# receiver_v2.net
KiCad netlist of a schematic drawn in EAGLE
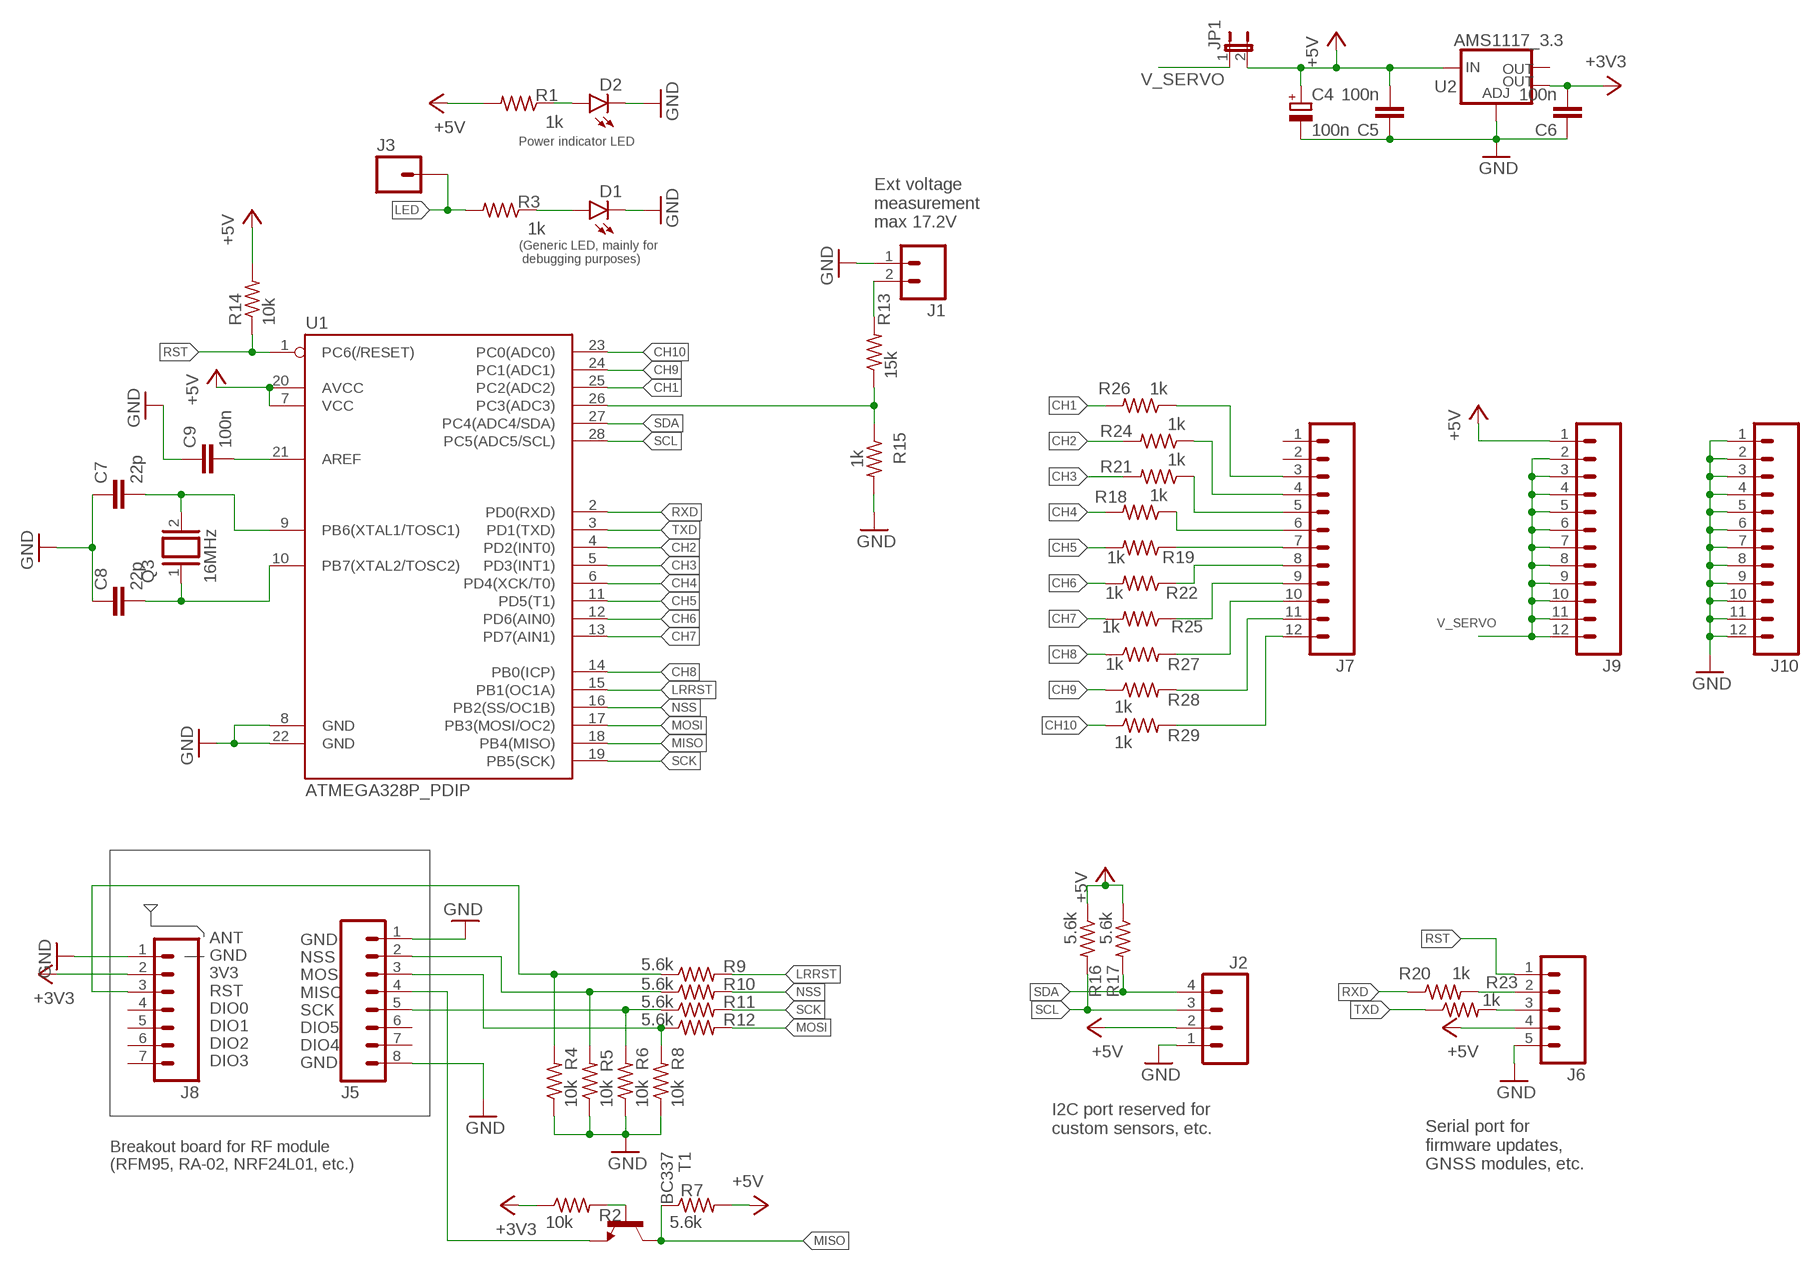
[diagram p0: schematic, sheet 1]

(export (version "E")
  (design (tool "Eeschema 10.0.6"))
  (components
    (comp (ref "C4")
      (value "100n")
      (footprint "eagle-import:E2,5-6E")
      (libsource (lib "eagle-import") (part "CPOL-EUE2,5-6E"))
    )
    (comp (ref "C5")
      (value "100n")
      (footprint "eagle-import:C050-024X044")
      (libsource (lib "eagle-import") (part "C-EU050-024X044"))
    )
    (comp (ref "C6")
      (value "100n")
      (footprint "eagle-import:C050-024X044")
      (libsource (lib "eagle-import") (part "C-EU050-024X044"))
    )
    (comp (ref "C7")
      (value "22p")
      (footprint "eagle-import:C050-024X044")
      (libsource (lib "eagle-import") (part "C-EU050-024X044"))
    )
    (comp (ref "C8")
      (value "22p")
      (footprint "eagle-import:C050-024X044")
      (libsource (lib "eagle-import") (part "C-EU050-024X044"))
    )
    (comp (ref "C9")
      (value "100n")
      (footprint "eagle-import:C050-024X044")
      (libsource (lib "eagle-import") (part "C-EU050-024X044"))
    )
    (comp (ref "D1")
      (value "LED3MM")
      (footprint "eagle-import:LED3MM")
      (libsource (lib "eagle-import") (part "LED3MM"))
    )
    (comp (ref "D2")
      (value "LED3MM")
      (footprint "eagle-import:LED3MM")
      (libsource (lib "eagle-import") (part "LED3MM"))
    )
    (comp (ref "J1")
      (value "M02PTH")
      (footprint "eagle-import:1X02")
      (libsource (lib "eagle-import") (part "M02PTH"))
    )
    (comp (ref "J2")
      (value "M04PTH")
      (footprint "eagle-import:1X04")
      (libsource (lib "eagle-import") (part "M04PTH"))
    )
    (comp (ref "J3")
      (value "M01PTH")
      (footprint "eagle-import:1X01")
      (libsource (lib "eagle-import") (part "M01PTH"))
    )
    (comp (ref "J5")
      (value "M08")
      (footprint "eagle-import:1X08_ROUND")
      (libsource (lib "eagle-import") (part "M08"))
    )
    (comp (ref "J6")
      (value "M05PTH")
      (footprint "eagle-import:1X05")
      (libsource (lib "eagle-import") (part "M05PTH"))
    )
    (comp (ref "J7")
      (value "M12PTH")
      (footprint "eagle-import:1X12")
      (libsource (lib "eagle-import") (part "M12PTH"))
    )
    (comp (ref "J8")
      (value "M07")
      (footprint "eagle-import:1X07")
      (libsource (lib "eagle-import") (part "M07"))
    )
    (comp (ref "J9")
      (value "M12PTH")
      (footprint "eagle-import:1X12")
      (libsource (lib "eagle-import") (part "M12PTH"))
    )
    (comp (ref "J10")
      (value "M12PTH")
      (footprint "eagle-import:1X12")
      (libsource (lib "eagle-import") (part "M12PTH"))
    )
    (comp (ref "JP1")
      (value "JP1E")
      (footprint "eagle-import:JP1")
      (libsource (lib "eagle-import") (part "JP1E"))
    )
    (comp (ref "Q3")
      (value "16MHz")
      (footprint "eagle-import:QS")
      (libsource (lib "eagle-import") (part "XTAL/S"))
    )
    (comp (ref "R1")
      (value "1k")
      (footprint "eagle-import:0204V")
      (libsource (lib "eagle-import") (part "R-US_0204/2V"))
    )
    (comp (ref "R2")
      (value "10k")
      (footprint "eagle-import:0207_15")
      (libsource (lib "eagle-import") (part "R-US_0207/15"))
    )
    (comp (ref "R3")
      (value "1k")
      (footprint "eagle-import:0204V")
      (libsource (lib "eagle-import") (part "R-US_0204/2V"))
    )
    (comp (ref "R4")
      (value "10k")
      (footprint "eagle-import:0204V")
      (libsource (lib "eagle-import") (part "R-US_0204/2V"))
    )
    (comp (ref "R5")
      (value "10k")
      (footprint "eagle-import:0204V")
      (libsource (lib "eagle-import") (part "R-US_0204/2V"))
    )
    (comp (ref "R6")
      (value "10k")
      (footprint "eagle-import:0204V")
      (libsource (lib "eagle-import") (part "R-US_0204/2V"))
    )
    (comp (ref "R7")
      (value "5.6k")
      (footprint "eagle-import:0204V")
      (libsource (lib "eagle-import") (part "R-US_0204/2V"))
    )
    (comp (ref "R8")
      (value "10k")
      (footprint "eagle-import:0204V")
      (libsource (lib "eagle-import") (part "R-US_0204/2V"))
    )
    (comp (ref "R9")
      (value "5.6k")
      (footprint "eagle-import:0204V")
      (libsource (lib "eagle-import") (part "R-US_0204/2V"))
    )
    (comp (ref "R10")
      (value "5.6k")
      (footprint "eagle-import:0204V")
      (libsource (lib "eagle-import") (part "R-US_0204/2V"))
    )
    (comp (ref "R11")
      (value "5.6k")
      (footprint "eagle-import:0204V")
      (libsource (lib "eagle-import") (part "R-US_0204/2V"))
    )
    (comp (ref "R12")
      (value "5.6k")
      (footprint "eagle-import:0204V")
      (libsource (lib "eagle-import") (part "R-US_0204/2V"))
    )
    (comp (ref "R13")
      (value "15k")
      (footprint "eagle-import:0204V")
      (libsource (lib "eagle-import") (part "R-US_0204/2V"))
    )
    (comp (ref "R14")
      (value "10k")
      (footprint "eagle-import:0204_7")
      (libsource (lib "eagle-import") (part "R-US_0204/7"))
    )
    (comp (ref "R15")
      (value "1k")
      (footprint "eagle-import:0204V")
      (libsource (lib "eagle-import") (part "R-US_0204/2V"))
    )
    (comp (ref "R16")
      (value "5.6k")
      (footprint "eagle-import:0204V")
      (libsource (lib "eagle-import") (part "R-US_0204/2V"))
    )
    (comp (ref "R17")
      (value "5.6k")
      (footprint "eagle-import:0204V")
      (libsource (lib "eagle-import") (part "R-US_0204/2V"))
    )
    (comp (ref "R18")
      (value "1k")
      (footprint "eagle-import:0204V")
      (libsource (lib "eagle-import") (part "R-US_0204/2V"))
    )
    (comp (ref "R19")
      (value "1k")
      (footprint "eagle-import:0204V")
      (libsource (lib "eagle-import") (part "R-US_0204/2V"))
    )
    (comp (ref "R20")
      (value "1k")
      (footprint "eagle-import:0204_7")
      (libsource (lib "eagle-import") (part "R-US_0204/7"))
    )
    (comp (ref "R21")
      (value "1k")
      (footprint "eagle-import:0204V")
      (libsource (lib "eagle-import") (part "R-US_0204/2V"))
    )
    (comp (ref "R22")
      (value "1k")
      (footprint "eagle-import:0204V")
      (libsource (lib "eagle-import") (part "R-US_0204/2V"))
    )
    (comp (ref "R23")
      (value "1k")
      (footprint "eagle-import:0204_7")
      (libsource (lib "eagle-import") (part "R-US_0204/7"))
    )
    (comp (ref "R24")
      (value "1k")
      (footprint "eagle-import:0204V")
      (libsource (lib "eagle-import") (part "R-US_0204/2V"))
    )
    (comp (ref "R25")
      (value "1k")
      (footprint "eagle-import:0204V")
      (libsource (lib "eagle-import") (part "R-US_0204/2V"))
    )
    (comp (ref "R26")
      (value "1k")
      (footprint "eagle-import:0204V")
      (libsource (lib "eagle-import") (part "R-US_0204/2V"))
    )
    (comp (ref "R27")
      (value "1k")
      (footprint "eagle-import:0204V")
      (libsource (lib "eagle-import") (part "R-US_0204/2V"))
    )
    (comp (ref "R28")
      (value "1k")
      (footprint "eagle-import:0204V")
      (libsource (lib "eagle-import") (part "R-US_0204/2V"))
    )
    (comp (ref "R29")
      (value "1k")
      (footprint "eagle-import:0204V")
      (libsource (lib "eagle-import") (part "R-US_0204/2V"))
    )
    (comp (ref "T1")
      (value "BC337")
      (footprint "eagle-import:TO92")
      (libsource (lib "eagle-import") (part "BC337"))
    )
    (comp (ref "U1")
      (value "ATMEGA328P_PDIP")
      (footprint "eagle-import:DIL28-3")
      (libsource (lib "eagle-import") (part "ATMEGA328P_PDIP"))
    )
    (comp (ref "U2")
      (value "AMS1117_3.3")
      (footprint "eagle-import:SOT223")
      (libsource (lib "eagle-import") (part "V_REG_LM1117SOT223"))
    )
  )
  (nets
    (net (code "1") (name "+3V3") (class "Default")
      (node (ref "C6") (pin "2") (pinfunction "2_2") (pintype "passive"))
      (node (ref "J8") (pin "2") (pinfunction "2_2") (pintype "passive"))
      (node (ref "R2") (pin "1") (pinfunction "1_1") (pintype "passive"))
      (node (ref "U2") (pin "4") (pinfunction "OUT_4") (pintype "output"))
    )
    (net (code "2") (name "+5V") (class "Default")
      (node (ref "C4") (pin "+") (pinfunction "+_+") (pintype "passive"))
      (node (ref "C5") (pin "2") (pinfunction "2_2") (pintype "passive"))
      (node (ref "J2") (pin "2") (pinfunction "2_2") (pintype "passive"))
      (node (ref "J6") (pin "4") (pinfunction "4_4") (pintype "passive"))
      (node (ref "J9") (pin "1") (pinfunction "1_1") (pintype "passive"))
      (node (ref "JP1") (pin "2") (pinfunction "2_2") (pintype "passive"))
      (node (ref "R1") (pin "2") (pinfunction "2_2") (pintype "passive"))
      (node (ref "R14") (pin "2") (pinfunction "2_2") (pintype "passive"))
      (node (ref "R16") (pin "1") (pinfunction "1_1") (pintype "passive"))
      (node (ref "R17") (pin "1") (pinfunction "1_1") (pintype "passive"))
      (node (ref "R7") (pin "2") (pinfunction "2_2") (pintype "passive"))
      (node (ref "U1") (pin "20") (pinfunction "AVCC_20") (pintype "bidirectional"))
      (node (ref "U1") (pin "7") (pinfunction "VCC_7") (pintype "bidirectional"))
      (node (ref "U2") (pin "3") (pinfunction "IN_3") (pintype "input"))
    )
    (net (code "3") (name "/V_SERVO") (class "Default")
      (node (ref "J9") (pin "10") (pinfunction "10_10") (pintype "passive"))
      (node (ref "J9") (pin "11") (pinfunction "11_11") (pintype "passive"))
      (node (ref "J9") (pin "12") (pinfunction "12_12") (pintype "passive"))
      (node (ref "J9") (pin "2") (pinfunction "2_2") (pintype "passive"))
      (node (ref "J9") (pin "3") (pinfunction "3_3") (pintype "passive"))
      (node (ref "J9") (pin "4") (pinfunction "4_4") (pintype "passive"))
      (node (ref "J9") (pin "5") (pinfunction "5_5") (pintype "passive"))
      (node (ref "J9") (pin "6") (pinfunction "6_6") (pintype "passive"))
      (node (ref "J9") (pin "7") (pinfunction "7_7") (pintype "passive"))
      (node (ref "J9") (pin "8") (pinfunction "8_8") (pintype "passive"))
      (node (ref "J9") (pin "9") (pinfunction "9_9") (pintype "passive"))
      (node (ref "JP1") (pin "1") (pinfunction "1_1") (pintype "passive"))
    )
    (net (code "4") (name "CH1") (class "Default")
      (node (ref "R26") (pin "2") (pinfunction "2_2") (pintype "passive"))
      (node (ref "U1") (pin "25") (pinfunction "PC2(ADC2)_25") (pintype "bidirectional"))
    )
    (net (code "5") (name "CH2") (class "Default")
      (node (ref "R24") (pin "2") (pinfunction "2_2") (pintype "passive"))
      (node (ref "U1") (pin "4") (pinfunction "PD2(INT0)_4") (pintype "bidirectional"))
    )
    (net (code "6") (name "CH3") (class "Default")
      (node (ref "R21") (pin "2") (pinfunction "2_2") (pintype "passive"))
      (node (ref "U1") (pin "5") (pinfunction "PD3(INT1)_5") (pintype "bidirectional"))
    )
    (net (code "7") (name "CH4") (class "Default")
      (node (ref "R18") (pin "2") (pinfunction "2_2") (pintype "passive"))
      (node (ref "U1") (pin "6") (pinfunction "PD4(XCK/T0)_6") (pintype "bidirectional"))
    )
    (net (code "8") (name "CH5") (class "Default")
      (node (ref "R19") (pin "2") (pinfunction "2_2") (pintype "passive"))
      (node (ref "U1") (pin "11") (pinfunction "PD5(T1)_11") (pintype "bidirectional"))
    )
    (net (code "9") (name "CH6") (class "Default")
      (node (ref "R22") (pin "2") (pinfunction "2_2") (pintype "passive"))
      (node (ref "U1") (pin "12") (pinfunction "PD6(AIN0)_12") (pintype "bidirectional"))
    )
    (net (code "10") (name "CH7") (class "Default")
      (node (ref "R25") (pin "2") (pinfunction "2_2") (pintype "passive"))
      (node (ref "U1") (pin "13") (pinfunction "PD7(AIN1)_13") (pintype "bidirectional"))
    )
    (net (code "11") (name "CH8") (class "Default")
      (node (ref "R27") (pin "1") (pinfunction "1_1") (pintype "passive"))
      (node (ref "U1") (pin "14") (pinfunction "PB0(ICP)_14") (pintype "bidirectional"))
    )
    (net (code "12") (name "CH9") (class "Default")
      (node (ref "R28") (pin "1") (pinfunction "1_1") (pintype "passive"))
      (node (ref "U1") (pin "24") (pinfunction "PC1(ADC1)_24") (pintype "bidirectional"))
    )
    (net (code "13") (name "CH10") (class "Default")
      (node (ref "R29") (pin "1") (pinfunction "1_1") (pintype "passive"))
      (node (ref "U1") (pin "23") (pinfunction "PC0(ADC0)_23") (pintype "bidirectional"))
    )
    (net (code "14") (name "GND") (class "Default")
      (node (ref "C4") (pin "-") (pinfunction "-_-") (pintype "passive"))
      (node (ref "C5") (pin "1") (pinfunction "1_1") (pintype "passive"))
      (node (ref "C6") (pin "1") (pinfunction "1_1") (pintype "passive"))
      (node (ref "C7") (pin "1") (pinfunction "1_1") (pintype "passive"))
      (node (ref "C8") (pin "1") (pinfunction "1_1") (pintype "passive"))
      (node (ref "C9") (pin "1") (pinfunction "1_1") (pintype "passive"))
      (node (ref "D1") (pin "K") (pinfunction "C_K") (pintype "passive"))
      (node (ref "D2") (pin "K") (pinfunction "C_K") (pintype "passive"))
      (node (ref "J1") (pin "1") (pinfunction "1_1") (pintype "passive"))
      (node (ref "J10") (pin "1") (pinfunction "1_1") (pintype "passive"))
      (node (ref "J10") (pin "10") (pinfunction "10_10") (pintype "passive"))
      (node (ref "J10") (pin "11") (pinfunction "11_11") (pintype "passive"))
      (node (ref "J10") (pin "12") (pinfunction "12_12") (pintype "passive"))
      (node (ref "J10") (pin "2") (pinfunction "2_2") (pintype "passive"))
      (node (ref "J10") (pin "3") (pinfunction "3_3") (pintype "passive"))
      (node (ref "J10") (pin "4") (pinfunction "4_4") (pintype "passive"))
      (node (ref "J10") (pin "5") (pinfunction "5_5") (pintype "passive"))
      (node (ref "J10") (pin "6") (pinfunction "6_6") (pintype "passive"))
      (node (ref "J10") (pin "7") (pinfunction "7_7") (pintype "passive"))
      (node (ref "J10") (pin "8") (pinfunction "8_8") (pintype "passive"))
      (node (ref "J10") (pin "9") (pinfunction "9_9") (pintype "passive"))
      (node (ref "J2") (pin "1") (pinfunction "1_1") (pintype "passive"))
      (node (ref "J5") (pin "1") (pinfunction "1_1") (pintype "passive"))
      (node (ref "J5") (pin "8") (pinfunction "8_8") (pintype "passive"))
      (node (ref "J6") (pin "5") (pinfunction "5_5") (pintype "passive"))
      (node (ref "J8") (pin "1") (pinfunction "1_1") (pintype "passive"))
      (node (ref "R15") (pin "2") (pinfunction "2_2") (pintype "passive"))
      (node (ref "R4") (pin "1") (pinfunction "1_1") (pintype "passive"))
      (node (ref "R5") (pin "1") (pinfunction "1_1") (pintype "passive"))
      (node (ref "R6") (pin "1") (pinfunction "1_1") (pintype "passive"))
      (node (ref "R8") (pin "1") (pinfunction "1_1") (pintype "passive"))
      (node (ref "U1") (pin "22") (pinfunction "GND_22") (pintype "bidirectional"))
      (node (ref "U1") (pin "8") (pinfunction "GND_8") (pintype "bidirectional"))
      (node (ref "U2") (pin "1") (pinfunction "ADJ_1") (pintype "input"))
    )
    (net (code "15") (name "LED") (class "Default")
      (node (ref "J3") (pin "1") (pinfunction "1_1") (pintype "passive"))
      (node (ref "R3") (pin "2") (pinfunction "2_2") (pintype "passive"))
    )
    (net (code "16") (name "LRRST") (class "Default")
      (node (ref "R9") (pin "2") (pinfunction "2_2") (pintype "passive"))
      (node (ref "U1") (pin "15") (pinfunction "PB1(OC1A)_15") (pintype "bidirectional"))
    )
    (net (code "17") (name "MISO") (class "Default")
      (node (ref "R7") (pin "1") (pinfunction "1_1") (pintype "passive"))
      (node (ref "T1") (pin "3") (pinfunction "C_3") (pintype "passive"))
      (node (ref "U1") (pin "18") (pinfunction "PB4(MISO)_18") (pintype "bidirectional"))
    )
    (net (code "18") (name "MOSI") (class "Default")
      (node (ref "R12") (pin "2") (pinfunction "2_2") (pintype "passive"))
      (node (ref "U1") (pin "17") (pinfunction "PB3(MOSI/OC2)_17") (pintype "bidirectional"))
    )
    (net (code "19") (name "NSS") (class "Default")
      (node (ref "R10") (pin "2") (pinfunction "2_2") (pintype "passive"))
      (node (ref "U1") (pin "16") (pinfunction "PB2(SS/OC1B)_16") (pintype "bidirectional"))
    )
    (net (code "20") (name "Net-(D1-PadA)") (class "Default")
      (node (ref "D1") (pin "A") (pinfunction "A_A") (pintype "passive"))
      (node (ref "R3") (pin "1") (pinfunction "1_1") (pintype "passive"))
    )
    (net (code "21") (name "Net-(D2-PadA)") (class "Default")
      (node (ref "D2") (pin "A") (pinfunction "A_A") (pintype "passive"))
      (node (ref "R1") (pin "1") (pinfunction "1_1") (pintype "passive"))
    )
    (net (code "22") (name "Net-(J1-Pad2)") (class "Default")
      (node (ref "J1") (pin "2") (pinfunction "2_2") (pintype "passive"))
      (node (ref "R13") (pin "2") (pinfunction "2_2") (pintype "passive"))
    )
    (net (code "23") (name "Net-(J5-Pad2)") (class "Default")
      (node (ref "J5") (pin "2") (pinfunction "2_2") (pintype "passive"))
      (node (ref "R10") (pin "1") (pinfunction "1_1") (pintype "passive"))
      (node (ref "R5") (pin "2") (pinfunction "2_2") (pintype "passive"))
    )
    (net (code "24") (name "Net-(J5-Pad3)") (class "Default")
      (node (ref "J5") (pin "3") (pinfunction "3_3") (pintype "passive"))
      (node (ref "R12") (pin "1") (pinfunction "1_1") (pintype "passive"))
      (node (ref "R8") (pin "2") (pinfunction "2_2") (pintype "passive"))
    )
    (net (code "25") (name "Net-(J5-Pad5)") (class "Default")
      (node (ref "J5") (pin "5") (pinfunction "5_5") (pintype "passive"))
      (node (ref "R11") (pin "1") (pinfunction "1_1") (pintype "passive"))
      (node (ref "R6") (pin "2") (pinfunction "2_2") (pintype "passive"))
    )
    (net (code "26") (name "Net-(J6-Pad2)") (class "Default")
      (node (ref "J6") (pin "2") (pinfunction "2_2") (pintype "passive"))
      (node (ref "R20") (pin "2") (pinfunction "2_2") (pintype "passive"))
    )
    (net (code "27") (name "Net-(J6-Pad3)") (class "Default")
      (node (ref "J6") (pin "3") (pinfunction "3_3") (pintype "passive"))
      (node (ref "R23") (pin "2") (pinfunction "2_2") (pintype "passive"))
    )
    (net (code "28") (name "Net-(J7-Pad3)") (class "Default")
      (node (ref "J7") (pin "3") (pinfunction "3_3") (pintype "passive"))
      (node (ref "R26") (pin "1") (pinfunction "1_1") (pintype "passive"))
    )
    (net (code "29") (name "Net-(J7-Pad4)") (class "Default")
      (node (ref "J7") (pin "4") (pinfunction "4_4") (pintype "passive"))
      (node (ref "R24") (pin "1") (pinfunction "1_1") (pintype "passive"))
    )
    (net (code "30") (name "Net-(J7-Pad5)") (class "Default")
      (node (ref "J7") (pin "5") (pinfunction "5_5") (pintype "passive"))
      (node (ref "R21") (pin "1") (pinfunction "1_1") (pintype "passive"))
    )
    (net (code "31") (name "Net-(J7-Pad6)") (class "Default")
      (node (ref "J7") (pin "6") (pinfunction "6_6") (pintype "passive"))
      (node (ref "R18") (pin "1") (pinfunction "1_1") (pintype "passive"))
    )
    (net (code "32") (name "Net-(J7-Pad7)") (class "Default")
      (node (ref "J7") (pin "7") (pinfunction "7_7") (pintype "passive"))
      (node (ref "R19") (pin "1") (pinfunction "1_1") (pintype "passive"))
    )
    (net (code "33") (name "Net-(J7-Pad8)") (class "Default")
      (node (ref "J7") (pin "8") (pinfunction "8_8") (pintype "passive"))
      (node (ref "R22") (pin "1") (pinfunction "1_1") (pintype "passive"))
    )
    (net (code "34") (name "Net-(J7-Pad9)") (class "Default")
      (node (ref "J7") (pin "9") (pinfunction "9_9") (pintype "passive"))
      (node (ref "R25") (pin "1") (pinfunction "1_1") (pintype "passive"))
    )
    (net (code "35") (name "Net-(J7-Pad10)") (class "Default")
      (node (ref "J7") (pin "10") (pinfunction "10_10") (pintype "passive"))
      (node (ref "R27") (pin "2") (pinfunction "2_2") (pintype "passive"))
    )
    (net (code "36") (name "Net-(J7-Pad11)") (class "Default")
      (node (ref "J7") (pin "11") (pinfunction "11_11") (pintype "passive"))
      (node (ref "R28") (pin "2") (pinfunction "2_2") (pintype "passive"))
    )
    (net (code "37") (name "Net-(J7-Pad12)") (class "Default")
      (node (ref "J7") (pin "12") (pinfunction "12_12") (pintype "passive"))
      (node (ref "R29") (pin "2") (pinfunction "2_2") (pintype "passive"))
    )
    (net (code "38") (name "Net-(J8-Pad3)") (class "Default")
      (node (ref "J8") (pin "3") (pinfunction "3_3") (pintype "passive"))
      (node (ref "R4") (pin "2") (pinfunction "2_2") (pintype "passive"))
      (node (ref "R9") (pin "1") (pinfunction "1_1") (pintype "passive"))
    )
    (net (code "39") (name "Net-(T1-B)") (class "Default")
      (node (ref "R2") (pin "2") (pinfunction "2_2") (pintype "passive"))
      (node (ref "T1") (pin "2") (pinfunction "B_2") (pintype "passive"))
    )
    (net (code "40") (name "Net-(T1-E)") (class "Default")
      (node (ref "J5") (pin "4") (pinfunction "4_4") (pintype "passive"))
      (node (ref "T1") (pin "1") (pinfunction "E_1") (pintype "passive"))
    )
    (net (code "41") (name "Net-(U1-AREF)") (class "Default")
      (node (ref "C9") (pin "2") (pinfunction "2_2") (pintype "passive"))
      (node (ref "U1") (pin "21") (pinfunction "AREF_21") (pintype "bidirectional"))
    )
    (net (code "42") (name "Net-(U1-PB6(XTAL1{slash}TOSC1))") (class "Default")
      (node (ref "C7") (pin "2") (pinfunction "2_2") (pintype "passive"))
      (node (ref "Q3") (pin "2") (pinfunction "2_2") (pintype "passive"))
      (node (ref "U1") (pin "9") (pinfunction "PB6(XTAL1/TOSC1)_9") (pintype "bidirectional"))
    )
    (net (code "43") (name "Net-(U1-PB7(XTAL2{slash}TOSC2))") (class "Default")
      (node (ref "C8") (pin "2") (pinfunction "2_2") (pintype "passive"))
      (node (ref "Q3") (pin "1") (pinfunction "1_1") (pintype "passive"))
      (node (ref "U1") (pin "10") (pinfunction "PB7(XTAL2/TOSC2)_10") (pintype "bidirectional"))
    )
    (net (code "44") (name "Net-(U1-PC3(ADC3))") (class "Default")
      (node (ref "R13") (pin "1") (pinfunction "1_1") (pintype "passive"))
      (node (ref "R15") (pin "1") (pinfunction "1_1") (pintype "passive"))
      (node (ref "U1") (pin "26") (pinfunction "PC3(ADC3)_26") (pintype "bidirectional"))
    )
    (net (code "45") (name "RST") (class "Default")
      (node (ref "J6") (pin "1") (pinfunction "1_1") (pintype "passive"))
      (node (ref "R14") (pin "1") (pinfunction "1_1") (pintype "passive"))
      (node (ref "U1") (pin "1") (pinfunction "PC6(/RESET)_1") (pintype "bidirectional"))
    )
    (net (code "46") (name "RXD") (class "Default")
      (node (ref "R20") (pin "1") (pinfunction "1_1") (pintype "passive"))
      (node (ref "U1") (pin "2") (pinfunction "PD0(RXD)_2") (pintype "bidirectional"))
    )
    (net (code "47") (name "SCK") (class "Default")
      (node (ref "R11") (pin "2") (pinfunction "2_2") (pintype "passive"))
      (node (ref "U1") (pin "19") (pinfunction "PB5(SCK)_19") (pintype "bidirectional"))
    )
    (net (code "48") (name "SCL") (class "Default")
      (node (ref "J2") (pin "3") (pinfunction "3_3") (pintype "passive"))
      (node (ref "R16") (pin "2") (pinfunction "2_2") (pintype "passive"))
      (node (ref "U1") (pin "28") (pinfunction "PC5(ADC5/SCL)_28") (pintype "bidirectional"))
    )
    (net (code "49") (name "SDA") (class "Default")
      (node (ref "J2") (pin "4") (pinfunction "4_4") (pintype "passive"))
      (node (ref "R17") (pin "2") (pinfunction "2_2") (pintype "passive"))
      (node (ref "U1") (pin "27") (pinfunction "PC4(ADC4/SDA)_27") (pintype "bidirectional"))
    )
    (net (code "50") (name "TXD") (class "Default")
      (node (ref "R23") (pin "1") (pinfunction "1_1") (pintype "passive"))
      (node (ref "U1") (pin "3") (pinfunction "PD1(TXD)_3") (pintype "bidirectional"))
    )
    (net (code "51") (name "unconnected-(J5-Pad6)") (class "Default")
      (node (ref "J5") (pin "6") (pinfunction "6_6") (pintype "passive"))
    )
    (net (code "52") (name "unconnected-(J5-Pad7)") (class "Default")
      (node (ref "J5") (pin "7") (pinfunction "7_7") (pintype "passive"))
    )
    (net (code "53") (name "unconnected-(J7-Pad1)") (class "Default")
      (node (ref "J7") (pin "1") (pinfunction "1_1") (pintype "passive"))
    )
    (net (code "54") (name "unconnected-(J7-Pad2)") (class "Default")
      (node (ref "J7") (pin "2") (pinfunction "2_2") (pintype "passive"))
    )
    (net (code "55") (name "unconnected-(J8-Pad4)") (class "Default")
      (node (ref "J8") (pin "4") (pinfunction "4_4") (pintype "passive"))
    )
    (net (code "56") (name "unconnected-(J8-Pad5)") (class "Default")
      (node (ref "J8") (pin "5") (pinfunction "5_5") (pintype "passive"))
    )
    (net (code "57") (name "unconnected-(J8-Pad6)") (class "Default")
      (node (ref "J8") (pin "6") (pinfunction "6_6") (pintype "passive"))
    )
    (net (code "58") (name "unconnected-(J8-Pad7)") (class "Default")
      (node (ref "J8") (pin "7") (pinfunction "7_7") (pintype "passive"))
    )
    (net (code "59") (name "unconnected-(U2-OUT-Pad2)") (class "Default")
      (node (ref "U2") (pin "2") (pinfunction "OUT_2") (pintype "output"))
    )
  )
)
